# OR_gate.net
KiCad netlist of a schematic drawn in EAGLE
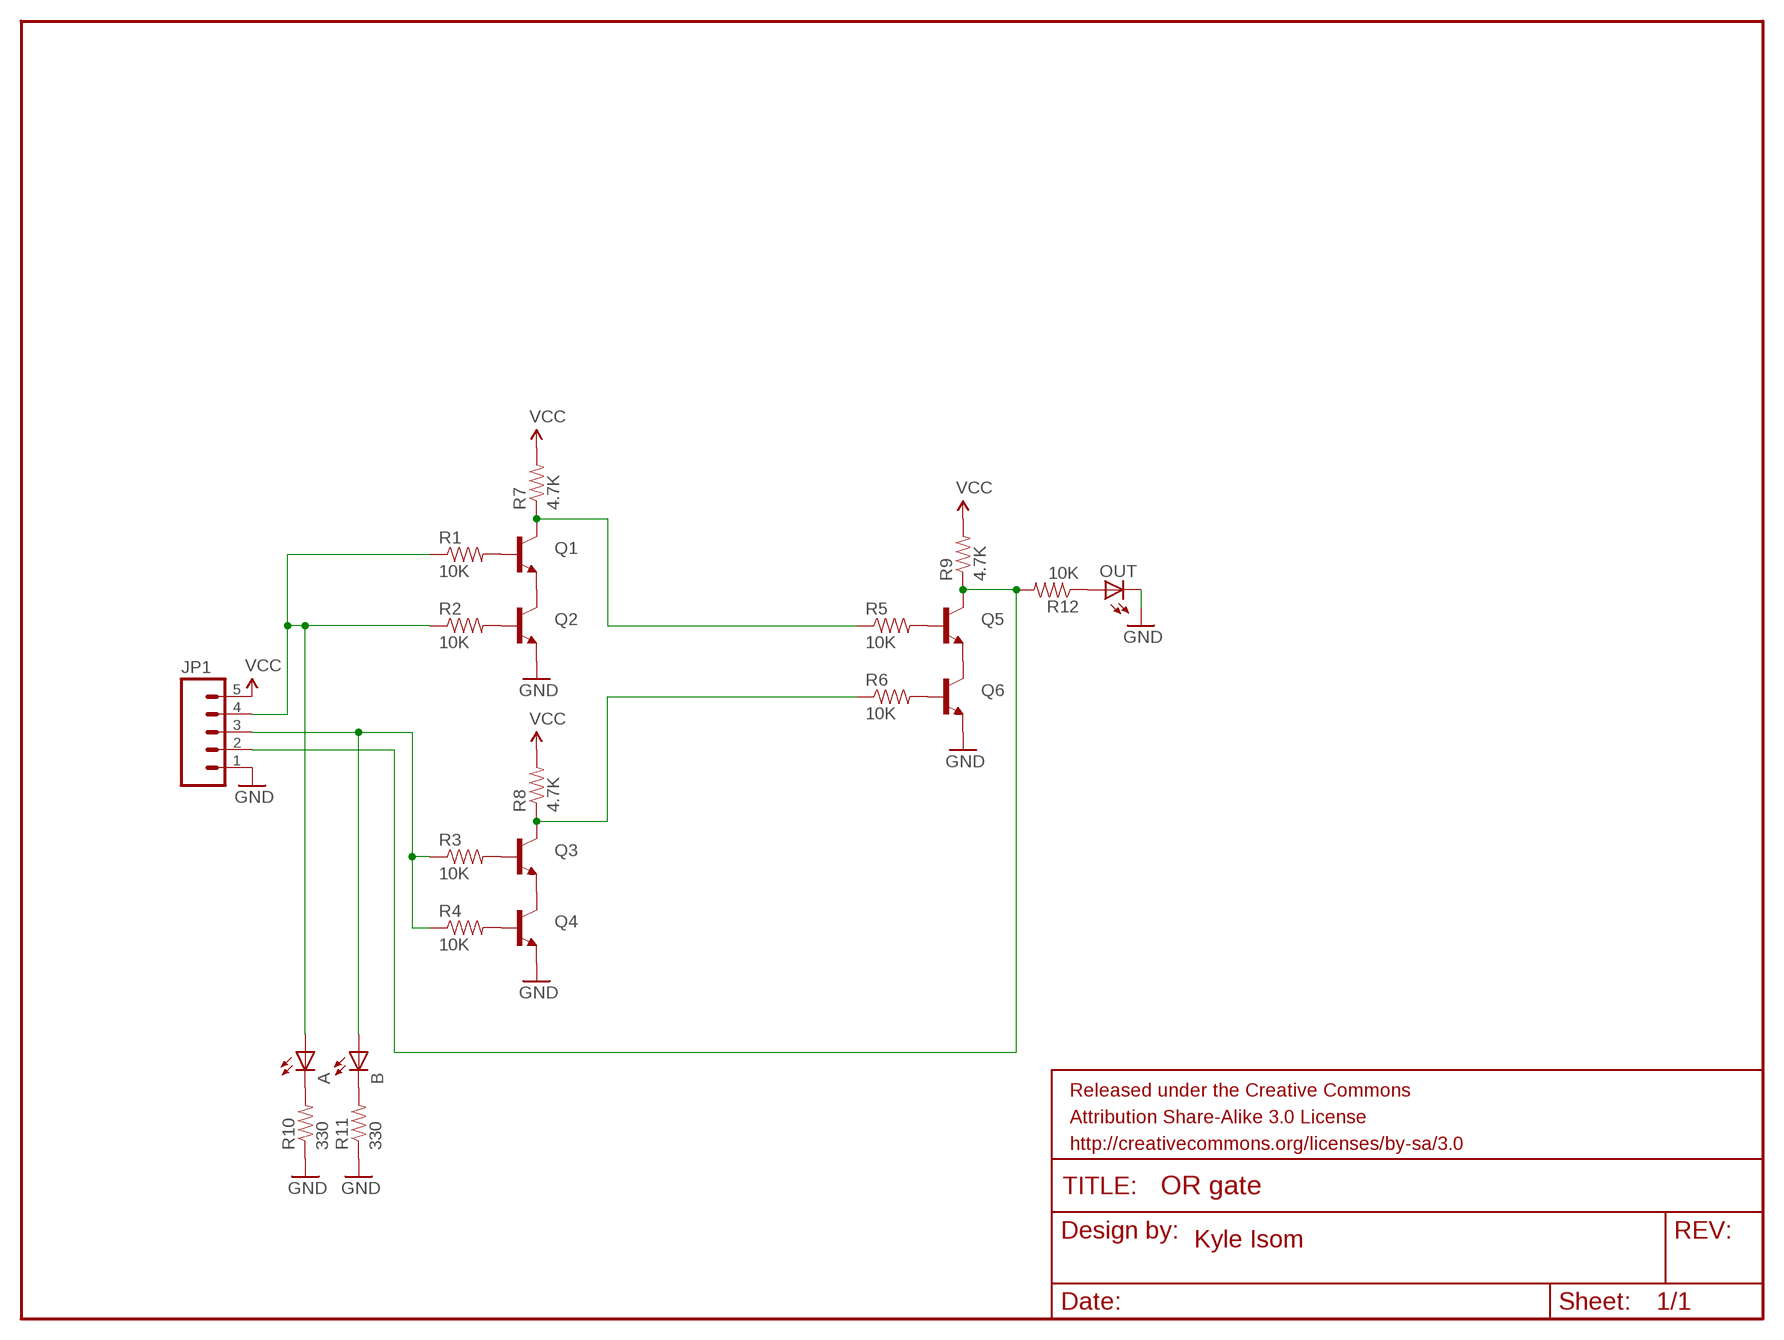
[diagram p0: schematic, sheet 1]

(export (version "E")
  (design (tool "Eeschema 10.0.6"))
  (components
    (comp (ref "A")
      (value "LED3MM")
      (footprint "eagle-import:LED3MM")
      (libsource (lib "eagle-import") (part "LED3MM"))
    )
    (comp (ref "B")
      (value "LED3MM")
      (footprint "eagle-import:LED3MM")
      (libsource (lib "eagle-import") (part "LED3MM"))
    )
    (comp (ref "FRAME1")
      (value "FRAME-LETTER")
      (footprint "eagle-import:CREATIVE_COMMONS")
      (libsource (lib "eagle-import") (part "FRAME-LETTER"))
    )
    (comp (ref "JP1")
      (value "M05LOCK")
      (footprint "eagle-import:1X05_LOCK")
      (libsource (lib "eagle-import") (part "M05LOCK"))
    )
    (comp (ref "OUT")
      (value "LED3MM")
      (footprint "eagle-import:LED3MM")
      (libsource (lib "eagle-import") (part "LED3MM"))
    )
    (comp (ref "Q1")
      (value "TRANSISTOR_NPNTO-92-AMMO")
      (footprint "eagle-import:TO-92-AMMO")
      (libsource (lib "eagle-import") (part "TRANSISTOR_NPNTO-92-AMMO"))
    )
    (comp (ref "Q2")
      (value "TRANSISTOR_NPNTO-92-AMMO")
      (footprint "eagle-import:TO-92-AMMO")
      (libsource (lib "eagle-import") (part "TRANSISTOR_NPNTO-92-AMMO"))
    )
    (comp (ref "Q3")
      (value "TRANSISTOR_NPNTO-92-AMMO")
      (footprint "eagle-import:TO-92-AMMO")
      (libsource (lib "eagle-import") (part "TRANSISTOR_NPNTO-92-AMMO"))
    )
    (comp (ref "Q4")
      (value "TRANSISTOR_NPNTO-92-AMMO")
      (footprint "eagle-import:TO-92-AMMO")
      (libsource (lib "eagle-import") (part "TRANSISTOR_NPNTO-92-AMMO"))
    )
    (comp (ref "Q5")
      (value "TRANSISTOR_NPNTO-92-AMMO")
      (footprint "eagle-import:TO-92-AMMO")
      (libsource (lib "eagle-import") (part "TRANSISTOR_NPNTO-92-AMMO"))
    )
    (comp (ref "Q6")
      (value "TRANSISTOR_NPNTO-92-AMMO")
      (footprint "eagle-import:TO-92-AMMO")
      (libsource (lib "eagle-import") (part "TRANSISTOR_NPNTO-92-AMMO"))
    )
    (comp (ref "R1")
      (value "10K")
      (footprint "eagle-import:AXIAL-0.4")
      (libsource (lib "eagle-import") (part "RESISTORPTH-1/4W"))
    )
    (comp (ref "R2")
      (value "10K")
      (footprint "eagle-import:AXIAL-0.4")
      (libsource (lib "eagle-import") (part "RESISTORPTH-1/4W"))
    )
    (comp (ref "R3")
      (value "10K")
      (footprint "eagle-import:AXIAL-0.4")
      (libsource (lib "eagle-import") (part "RESISTORPTH-1/4W"))
    )
    (comp (ref "R4")
      (value "10K")
      (footprint "eagle-import:AXIAL-0.4")
      (libsource (lib "eagle-import") (part "RESISTORPTH-1/4W"))
    )
    (comp (ref "R5")
      (value "10K")
      (footprint "eagle-import:AXIAL-0.4")
      (libsource (lib "eagle-import") (part "RESISTORPTH-1/4W"))
    )
    (comp (ref "R6")
      (value "10K")
      (footprint "eagle-import:AXIAL-0.4")
      (libsource (lib "eagle-import") (part "RESISTORPTH-1/4W"))
    )
    (comp (ref "R7")
      (value "4.7K")
      (footprint "eagle-import:AXIAL-0.4")
      (libsource (lib "eagle-import") (part "RESISTORPTH-1/4W"))
    )
    (comp (ref "R8")
      (value "4.7K")
      (footprint "eagle-import:AXIAL-0.4")
      (libsource (lib "eagle-import") (part "RESISTORPTH-1/4W"))
    )
    (comp (ref "R9")
      (value "4.7K")
      (footprint "eagle-import:AXIAL-0.4")
      (libsource (lib "eagle-import") (part "RESISTORPTH-1/4W"))
    )
    (comp (ref "R10")
      (value "330")
      (footprint "eagle-import:AXIAL-0.4")
      (libsource (lib "eagle-import") (part "RESISTORPTH-1/4W"))
    )
    (comp (ref "R11")
      (value "330")
      (footprint "eagle-import:AXIAL-0.4")
      (libsource (lib "eagle-import") (part "RESISTORPTH-1/4W"))
    )
    (comp (ref "R12")
      (value "10K")
      (footprint "eagle-import:AXIAL-0.4")
      (libsource (lib "eagle-import") (part "RESISTORPTH-1/4W"))
    )
  )
  (nets
    (net (code "1") (name "GND") (class "Default")
      (node (ref "JP1") (pin "1") (pinfunction "1_1") (pintype "passive"))
      (node (ref "OUT") (pin "K") (pinfunction "C_K") (pintype "passive"))
      (node (ref "Q2") (pin "1") (pinfunction "E_1") (pintype "passive"))
      (node (ref "Q4") (pin "1") (pinfunction "E_1") (pintype "passive"))
      (node (ref "Q6") (pin "1") (pinfunction "E_1") (pintype "passive"))
      (node (ref "R10") (pin "P$1") (pinfunction "1_P$1") (pintype "passive"))
      (node (ref "R11") (pin "P$1") (pinfunction "1_P$1") (pintype "passive"))
    )
    (net (code "2") (name "Net-(A-C)") (class "Default")
      (node (ref "A") (pin "K") (pinfunction "C_K") (pintype "passive"))
      (node (ref "R10") (pin "P$2") (pinfunction "2_P$2") (pintype "passive"))
    )
    (net (code "3") (name "Net-(B-C)") (class "Default")
      (node (ref "B") (pin "K") (pinfunction "C_K") (pintype "passive"))
      (node (ref "R11") (pin "P$2") (pinfunction "2_P$2") (pintype "passive"))
    )
    (net (code "4") (name "Net-(Q1-B)") (class "Default")
      (node (ref "Q1") (pin "2") (pinfunction "B_2") (pintype "passive"))
      (node (ref "R1") (pin "P$2") (pinfunction "2_P$2") (pintype "passive"))
    )
    (net (code "5") (name "Net-(Q1-C)") (class "Default")
      (node (ref "Q1") (pin "3") (pinfunction "C_3") (pintype "passive"))
      (node (ref "R5") (pin "P$1") (pinfunction "1_P$1") (pintype "passive"))
      (node (ref "R7") (pin "P$1") (pinfunction "1_P$1") (pintype "passive"))
    )
    (net (code "6") (name "Net-(Q1-E)") (class "Default")
      (node (ref "Q1") (pin "1") (pinfunction "E_1") (pintype "passive"))
      (node (ref "Q2") (pin "3") (pinfunction "C_3") (pintype "passive"))
    )
    (net (code "7") (name "Net-(Q2-B)") (class "Default")
      (node (ref "Q2") (pin "2") (pinfunction "B_2") (pintype "passive"))
      (node (ref "R2") (pin "P$2") (pinfunction "2_P$2") (pintype "passive"))
    )
    (net (code "8") (name "Net-(Q3-B)") (class "Default")
      (node (ref "Q3") (pin "2") (pinfunction "B_2") (pintype "passive"))
      (node (ref "R3") (pin "P$2") (pinfunction "2_P$2") (pintype "passive"))
    )
    (net (code "9") (name "Net-(Q3-C)") (class "Default")
      (node (ref "Q3") (pin "3") (pinfunction "C_3") (pintype "passive"))
      (node (ref "R6") (pin "P$1") (pinfunction "1_P$1") (pintype "passive"))
      (node (ref "R8") (pin "P$1") (pinfunction "1_P$1") (pintype "passive"))
    )
    (net (code "10") (name "Net-(Q3-E)") (class "Default")
      (node (ref "Q3") (pin "1") (pinfunction "E_1") (pintype "passive"))
      (node (ref "Q4") (pin "3") (pinfunction "C_3") (pintype "passive"))
    )
    (net (code "11") (name "Net-(Q4-B)") (class "Default")
      (node (ref "Q4") (pin "2") (pinfunction "B_2") (pintype "passive"))
      (node (ref "R4") (pin "P$2") (pinfunction "2_P$2") (pintype "passive"))
    )
    (net (code "12") (name "Net-(Q5-B)") (class "Default")
      (node (ref "Q5") (pin "2") (pinfunction "B_2") (pintype "passive"))
      (node (ref "R5") (pin "P$2") (pinfunction "2_P$2") (pintype "passive"))
    )
    (net (code "13") (name "Net-(Q5-C)") (class "Default")
      (node (ref "JP1") (pin "2") (pinfunction "2_2") (pintype "passive"))
      (node (ref "Q5") (pin "3") (pinfunction "C_3") (pintype "passive"))
      (node (ref "R12") (pin "P$2") (pinfunction "2_P$2") (pintype "passive"))
      (node (ref "R9") (pin "P$1") (pinfunction "1_P$1") (pintype "passive"))
    )
    (net (code "14") (name "Net-(Q5-E)") (class "Default")
      (node (ref "Q5") (pin "1") (pinfunction "E_1") (pintype "passive"))
      (node (ref "Q6") (pin "3") (pinfunction "C_3") (pintype "passive"))
    )
    (net (code "15") (name "Net-(Q6-B)") (class "Default")
      (node (ref "Q6") (pin "2") (pinfunction "B_2") (pintype "passive"))
      (node (ref "R6") (pin "P$2") (pinfunction "2_P$2") (pintype "passive"))
    )
    (net (code "16") (name "Net-(R1-1)") (class "Default")
      (node (ref "A") (pin "A") (pinfunction "A_A") (pintype "passive"))
      (node (ref "JP1") (pin "4") (pinfunction "4_4") (pintype "passive"))
      (node (ref "R1") (pin "P$1") (pinfunction "1_P$1") (pintype "passive"))
      (node (ref "R2") (pin "P$1") (pinfunction "1_P$1") (pintype "passive"))
    )
    (net (code "17") (name "Net-(R3-1)") (class "Default")
      (node (ref "B") (pin "A") (pinfunction "A_A") (pintype "passive"))
      (node (ref "JP1") (pin "3") (pinfunction "3_3") (pintype "passive"))
      (node (ref "R3") (pin "P$1") (pinfunction "1_P$1") (pintype "passive"))
      (node (ref "R4") (pin "P$1") (pinfunction "1_P$1") (pintype "passive"))
    )
    (net (code "18") (name "Net-(R12-1)") (class "Default")
      (node (ref "OUT") (pin "A") (pinfunction "A_A") (pintype "passive"))
      (node (ref "R12") (pin "P$1") (pinfunction "1_P$1") (pintype "passive"))
    )
    (net (code "19") (name "VCC") (class "Default")
      (node (ref "JP1") (pin "5") (pinfunction "5_5") (pintype "passive"))
      (node (ref "R7") (pin "P$2") (pinfunction "2_P$2") (pintype "passive"))
      (node (ref "R8") (pin "P$2") (pinfunction "2_P$2") (pintype "passive"))
      (node (ref "R9") (pin "P$2") (pinfunction "2_P$2") (pintype "passive"))
    )
  )
)
